# espButton.net
KiCad netlist of a schematic drawn in EAGLE
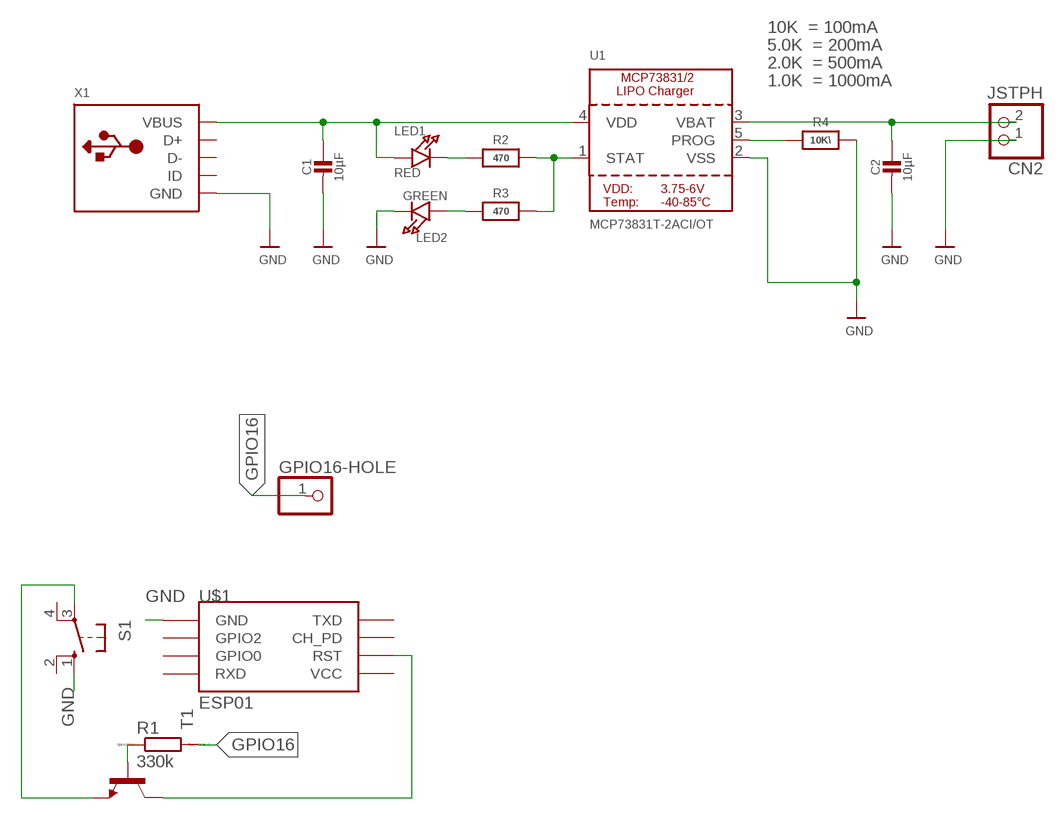
[diagram p0: schematic, sheet 1]

(export (version "E")
  (design (tool "Eeschema 10.0.6"))
  (components
    (comp (ref "C1")
      (value "10µF")
      (footprint "eagle-import:0805-NO")
      (libsource (lib "eagle-import") (part "CAP_CERAMIC0805-NOOUTLINE"))
    )
    (comp (ref "C2")
      (value "10µF")
      (footprint "eagle-import:0805-NO")
      (libsource (lib "eagle-import") (part "CAP_CERAMIC0805-NOOUTLINE"))
    )
    (comp (ref "CN2")
      (value "JSTPH")
      (footprint "eagle-import:JSTPH2")
      (libsource (lib "eagle-import") (part "JST_2PIN"))
    )
    (comp (ref "GPIO16-HOLE")
      (value "PINHD-1X1CB")
      (footprint "eagle-import:1X01-CLEANBIG")
      (libsource (lib "eagle-import") (part "PINHD-1X1CB"))
    )
    (comp (ref "LED1")
      (value "RED")
      (footprint "eagle-import:CHIPLED_0805_NOOUTLINE")
      (libsource (lib "eagle-import") (part "LED0805_NOOUTLINE"))
    )
    (comp (ref "LED2")
      (value "GREEN")
      (footprint "eagle-import:CHIPLED_0805_NOOUTLINE")
      (libsource (lib "eagle-import") (part "LED0805_NOOUTLINE"))
    )
    (comp (ref "R1")
      (value "330k")
      (footprint "eagle-import:0204_7")
      (libsource (lib "eagle-import") (part "R0204/7"))
    )
    (comp (ref "R2")
      (value "470")
      (footprint "eagle-import:0805-NO")
      (libsource (lib "eagle-import") (part "RESISTOR0805_NOOUTLINE"))
    )
    (comp (ref "R3")
      (value "470")
      (footprint "eagle-import:0805-NO")
      (libsource (lib "eagle-import") (part "RESISTOR0805_NOOUTLINE"))
    )
    (comp (ref "R4")
      (value "10K\\")
      (footprint "eagle-import:0805-NO")
      (libsource (lib "eagle-import") (part "RESISTOR0805_NOOUTLINE"))
    )
    (comp (ref "S1")
      (value "10-XX")
      (footprint "eagle-import:B3F-10XX")
      (fields (field (name "MPN") "B3F-1000"))
      (libsource (lib "eagle-import") (part "10-XX"))
    )
    (comp (ref "T1")
      (value "2N4401-NPN-TO92-EBC")
      (footprint "eagle-import:TO92-EBC")
      (libsource (lib "eagle-import") (part "-NPN-TO92-EBC2N4401"))
    )
    (comp (ref "U$1")
      (value "ESP01")
      (footprint "eagle-import:ESP01")
      (libsource (lib "eagle-import") (part "ESP01"))
    )
    (comp (ref "U1")
      (value "MCP73831T-2ACI/OT")
      (footprint "eagle-import:SOT23-5")
      (libsource (lib "eagle-import") (part "MCP73831/2"))
    )
    (comp (ref "X1")
      (value "USBMICRO_20329")
      (footprint "eagle-import:4UCONN_20329")
      (libsource (lib "eagle-import") (part "USBMICRO_20329"))
    )
  )
  (nets
    (net (code "1") (name "GND") (class "Default")
      (node (ref "C1") (pin "2") (pinfunction "2_2") (pintype "passive"))
      (node (ref "C2") (pin "2") (pinfunction "2_2") (pintype "passive"))
      (node (ref "CN2") (pin "1") (pinfunction "1_1") (pintype "passive"))
      (node (ref "LED2") (pin "C") (pinfunction "C_C") (pintype "passive"))
      (node (ref "R4") (pin "2") (pinfunction "2_2") (pintype "passive"))
      (node (ref "S1") (pin "1") (pinfunction "S_1") (pintype "passive"))
      (node (ref "U$1") (pin "GND") (pinfunction "GND_GND") (pintype "bidirectional"))
      (node (ref "U1") (pin "2") (pinfunction "VSS_2") (pintype "power_in"))
      (node (ref "X1") (pin "BASE@1") (pinfunction "GND_BASE@1") (pintype "power_in"))
      (node (ref "X1") (pin "BASE@2") (pinfunction "GND_BASE@2") (pintype "power_in"))
      (node (ref "X1") (pin "GND") (pinfunction "GND_GND") (pintype "power_in"))
      (node (ref "X1") (pin "SPRT@1") (pinfunction "GND_SPRT@1") (pintype "power_in"))
      (node (ref "X1") (pin "SPRT@2") (pinfunction "GND_SPRT@2") (pintype "power_in"))
      (node (ref "X1") (pin "SPRT@3") (pinfunction "GND_SPRT@3") (pintype "power_in"))
      (node (ref "X1") (pin "SPRT@4") (pinfunction "GND_SPRT@4") (pintype "power_in"))
    )
    (net (code "2") (name "GPIO16") (class "Default")
      (node (ref "GPIO16-HOLE") (pin "1") (pinfunction "1_1") (pintype "passive"))
      (node (ref "R1") (pin "2") (pinfunction "2_2") (pintype "passive"))
    )
    (net (code "3") (name "Net-(LED1-PadC)") (class "Default")
      (node (ref "LED1") (pin "C") (pinfunction "C_C") (pintype "passive"))
      (node (ref "R2") (pin "1") (pinfunction "1_1") (pintype "passive"))
    )
    (net (code "4") (name "Net-(LED2-PadA)") (class "Default")
      (node (ref "LED2") (pin "A") (pinfunction "A_A") (pintype "passive"))
      (node (ref "R3") (pin "1") (pinfunction "1_1") (pintype "passive"))
    )
    (net (code "5") (name "Net-(R1-Pad1)") (class "Default")
      (node (ref "R1") (pin "1") (pinfunction "1_1") (pintype "passive"))
      (node (ref "T1") (pin "B") (pinfunction "B_B") (pintype "passive"))
    )
    (net (code "6") (name "Net-(S1-P)") (class "Default")
      (node (ref "S1") (pin "3") (pinfunction "P_3") (pintype "passive"))
      (node (ref "T1") (pin "E") (pinfunction "E_E") (pintype "passive"))
    )
    (net (code "7") (name "Net-(T1-PadC)") (class "Default")
      (node (ref "T1") (pin "C") (pinfunction "C_C") (pintype "passive"))
      (node (ref "U$1") (pin "RST") (pinfunction "RST_RST") (pintype "bidirectional"))
    )
    (net (code "8") (name "Net-(U1-PROG)") (class "Default")
      (node (ref "R4") (pin "1") (pinfunction "1_1") (pintype "passive"))
      (node (ref "U1") (pin "5") (pinfunction "PROG_5") (pintype "input"))
    )
    (net (code "9") (name "Net-(U1-STAT)") (class "Default")
      (node (ref "R2") (pin "2") (pinfunction "2_2") (pintype "passive"))
      (node (ref "R3") (pin "2") (pinfunction "2_2") (pintype "passive"))
      (node (ref "U1") (pin "1") (pinfunction "STAT_1") (pintype "output"))
    )
    (net (code "10") (name "Net-(U1-VBAT)") (class "Default")
      (node (ref "C2") (pin "1") (pinfunction "1_1") (pintype "passive"))
      (node (ref "CN2") (pin "2") (pinfunction "2_2") (pintype "passive"))
      (node (ref "U1") (pin "3") (pinfunction "VBAT_3") (pintype "power_in"))
    )
    (net (code "11") (name "Net-(U1-VDD)") (class "Default")
      (node (ref "C1") (pin "1") (pinfunction "1_1") (pintype "passive"))
      (node (ref "LED1") (pin "A") (pinfunction "A_A") (pintype "passive"))
      (node (ref "U1") (pin "4") (pinfunction "VDD_4") (pintype "power_in"))
      (node (ref "X1") (pin "VBUS") (pinfunction "VBUS_VBUS") (pintype "power_in"))
    )
    (net (code "12") (name "unconnected-(S1-P1-Pad4)") (class "Default")
      (node (ref "S1") (pin "4") (pinfunction "P1_4") (pintype "passive"))
    )
    (net (code "13") (name "unconnected-(S1-S1-Pad2)") (class "Default")
      (node (ref "S1") (pin "2") (pinfunction "S1_2") (pintype "passive"))
    )
    (net (code "14") (name "unconnected-(U$1-PadCH_PD)") (class "Default")
      (node (ref "U$1") (pin "CH_PD") (pinfunction "CH_PD_CH_PD") (pintype "bidirectional"))
    )
    (net (code "15") (name "unconnected-(U$1-PadGPIO0)") (class "Default")
      (node (ref "U$1") (pin "GPIO0") (pinfunction "GPIO0_GPIO0") (pintype "bidirectional"))
    )
    (net (code "16") (name "unconnected-(U$1-PadGPIO2)") (class "Default")
      (node (ref "U$1") (pin "GPIO2") (pinfunction "GPIO2_GPIO2") (pintype "bidirectional"))
    )
    (net (code "17") (name "unconnected-(U$1-PadVCC)") (class "Default")
      (node (ref "U$1") (pin "VCC") (pinfunction "VCC_VCC") (pintype "bidirectional"))
    )
    (net (code "18") (name "unconnected-(U$1-RXD-PadRX)") (class "Default")
      (node (ref "U$1") (pin "RX") (pinfunction "RXD_RX") (pintype "bidirectional"))
    )
    (net (code "19") (name "unconnected-(U$1-TXD-PadTX)") (class "Default")
      (node (ref "U$1") (pin "TX") (pinfunction "TXD_TX") (pintype "bidirectional"))
    )
    (net (code "20") (name "unconnected-(X1-PadD+)") (class "Default")
      (node (ref "X1") (pin "D+") (pinfunction "D+_D+") (pintype "bidirectional"))
    )
    (net (code "21") (name "unconnected-(X1-PadD-)") (class "Default")
      (node (ref "X1") (pin "D-") (pinfunction "D-_D-") (pintype "bidirectional"))
    )
    (net (code "22") (name "unconnected-(X1-PadID)") (class "Default")
      (node (ref "X1") (pin "ID") (pinfunction "ID_ID") (pintype "bidirectional"))
    )
  )
)
